# TI_POW.net
KiCad netlist of a schematic drawn in Altium Designer
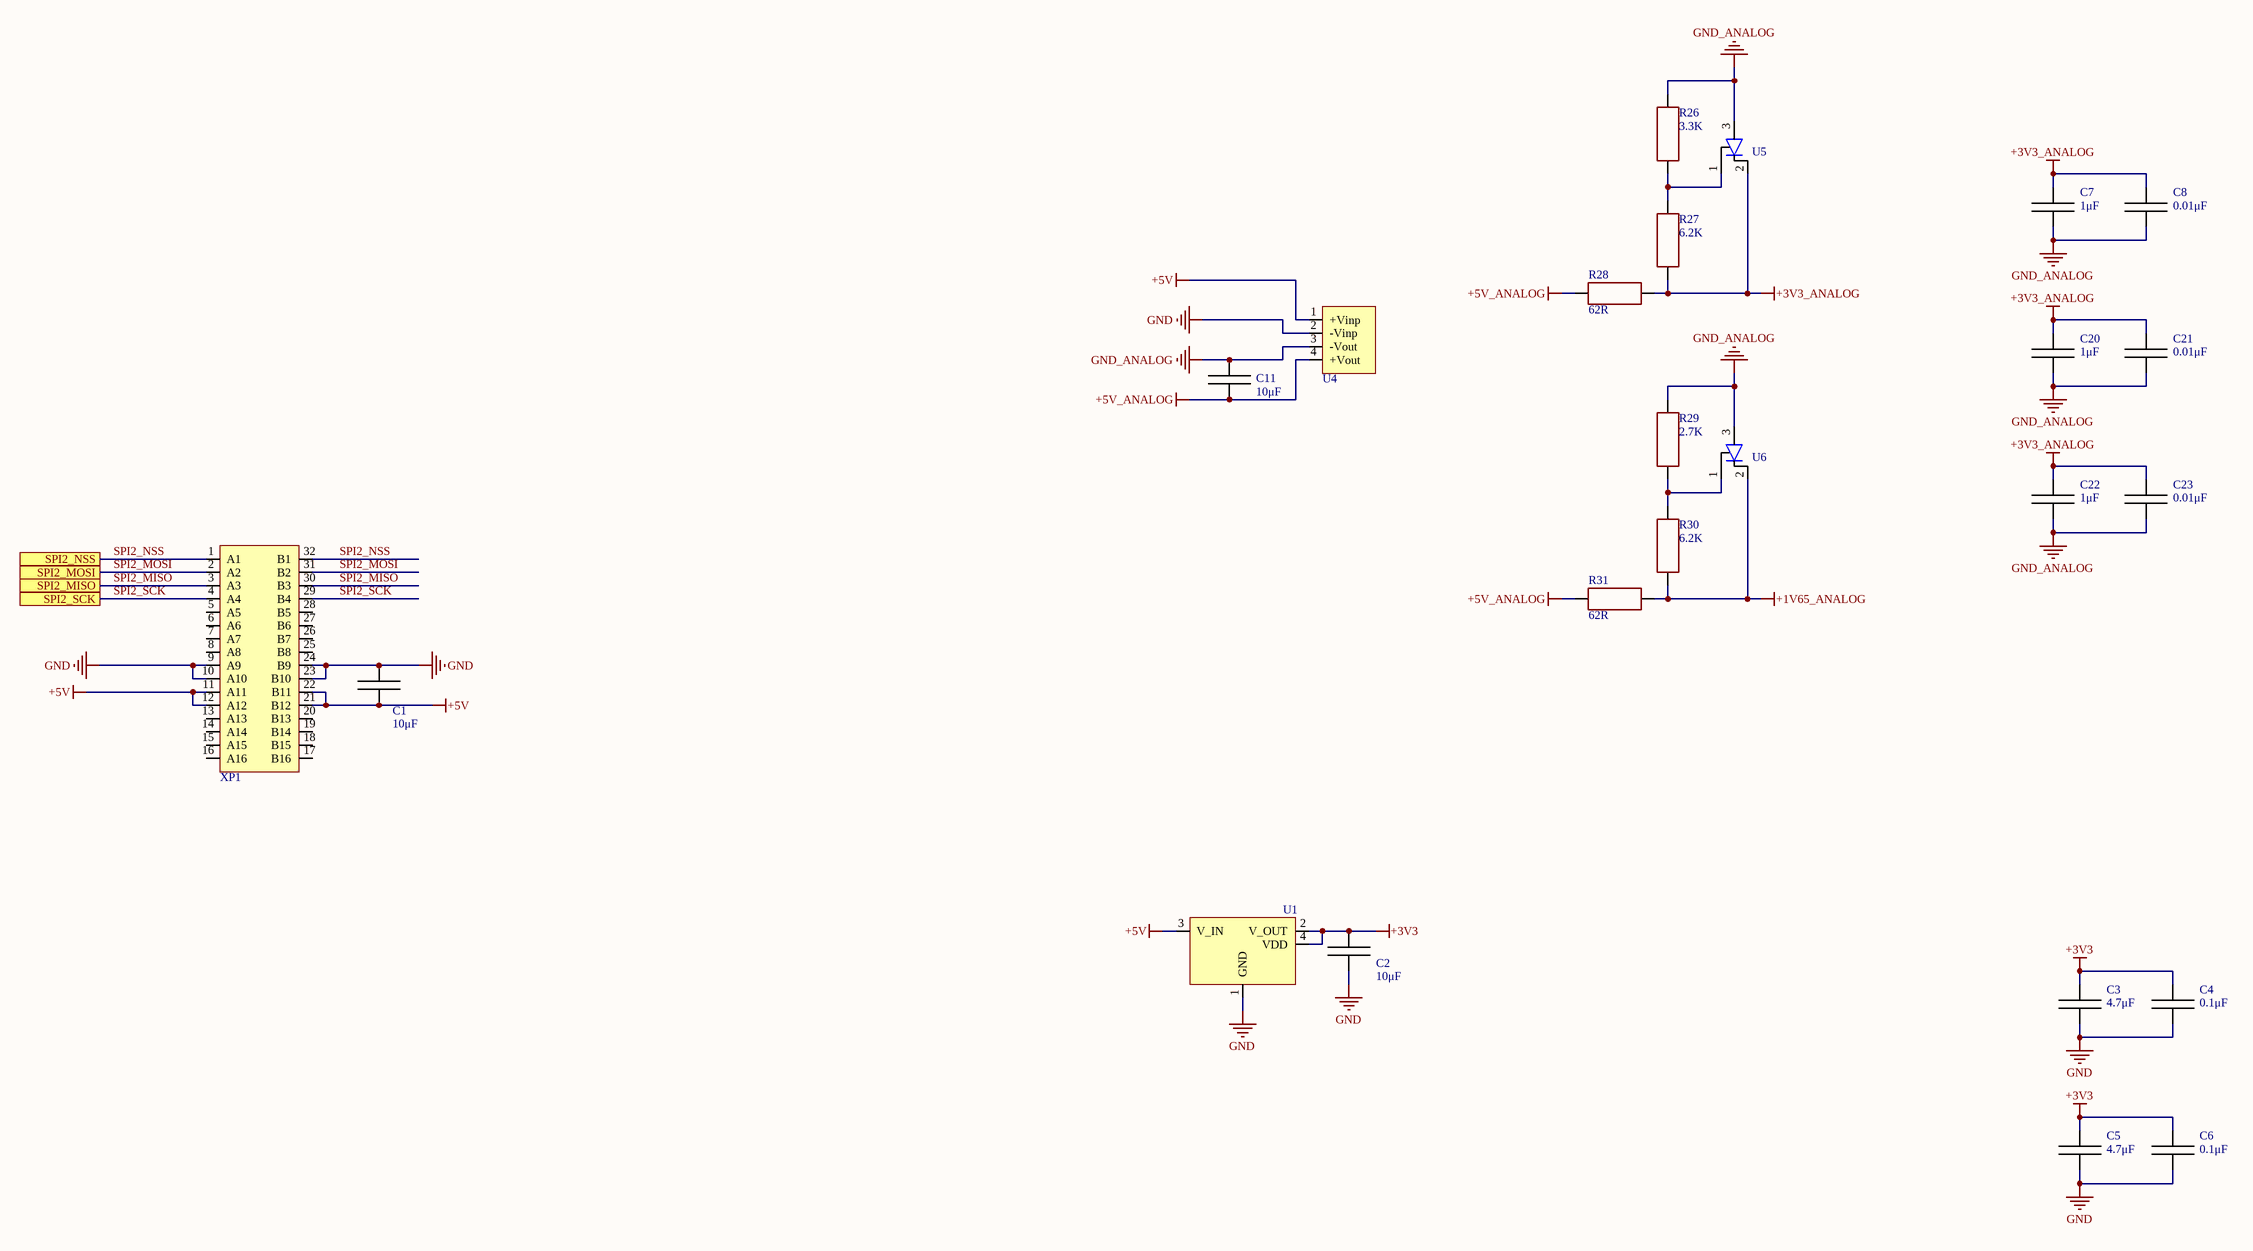
[diagram p0: TI_POW.SchDoc]

(export (version "E")
  (design (tool "Eeschema 10.0.6"))
  (components
    (comp (ref "C1")
      (value "10μF")
      (footprint "CAP: 2220")
      (fields (field (name "VOLTAGE") "16V") (field (name "Comment") "Cap_2220"))
      (libsource (lib "capacitor") (part "Cap_2220"))
    )
    (comp (ref "C2")
      (value "10μF")
      (footprint "CAP: 2220")
      (fields (field (name "VOLTAGE") "16V") (field (name "Comment") "Cap_2220"))
      (libsource (lib "capacitor") (part "Cap_2220"))
    )
    (comp (ref "C3")
      (value "4.7μF")
      (footprint "CAP: 0603")
      (fields (field (name "VOLTAGE") "25V") (field (name "Comment") "Cap_0603"))
      (libsource (lib "capacitor") (part "Cap_0603"))
    )
    (comp (ref "C4")
      (value "0.1μF")
      (footprint "CAP: 0603")
      (fields (field (name "VOLTAGE") "16V") (field (name "Comment") "Cap_0603"))
      (libsource (lib "capacitor") (part "Cap_0603"))
    )
    (comp (ref "C5")
      (value "4.7μF")
      (footprint "CAP: 0603")
      (fields (field (name "VOLTAGE") "25V") (field (name "Comment") "Cap_0603"))
      (libsource (lib "capacitor") (part "Cap_0603"))
    )
    (comp (ref "C6")
      (value "0.1μF")
      (footprint "CAP: 0603")
      (fields (field (name "VOLTAGE") "16V") (field (name "Comment") "Cap_0603"))
      (libsource (lib "capacitor") (part "Cap_0603"))
    )
    (comp (ref "C7")
      (value "1μF")
      (footprint "CAP: 0603")
      (fields (field (name "VOLTAGE") "16V") (field (name "Comment") "Cap_0603"))
      (libsource (lib "capacitor") (part "Cap_0603"))
    )
    (comp (ref "C8")
      (value "0.01μF")
      (footprint "CAP: 0603")
      (fields (field (name "VOLTAGE") "50V") (field (name "Comment") "Cap_0603"))
      (libsource (lib "capacitor") (part "Cap_0603"))
    )
    (comp (ref "C11")
      (value "10μF")
      (footprint "CAP: 2220")
      (fields (field (name "VOLTAGE") "16V") (field (name "Comment") "Cap_2220"))
      (libsource (lib "capacitor") (part "Cap_2220"))
    )
    (comp (ref "C20")
      (value "1μF")
      (footprint "CAP: 0603")
      (fields (field (name "VOLTAGE") "16V") (field (name "Comment") "Cap_0603"))
      (libsource (lib "capacitor") (part "Cap_0603"))
    )
    (comp (ref "C21")
      (value "0.01μF")
      (footprint "CAP: 0603")
      (fields (field (name "VOLTAGE") "50V") (field (name "Comment") "Cap_0603"))
      (libsource (lib "capacitor") (part "Cap_0603"))
    )
    (comp (ref "C22")
      (value "1μF")
      (footprint "CAP: 0603")
      (fields (field (name "VOLTAGE") "16V") (field (name "Comment") "Cap_0603"))
      (libsource (lib "capacitor") (part "Cap_0603"))
    )
    (comp (ref "C23")
      (value "0.01μF")
      (footprint "CAP: 0603")
      (fields (field (name "VOLTAGE") "50V") (field (name "Comment") "Cap_0603"))
      (libsource (lib "capacitor") (part "Cap_0603"))
    )
    (comp (ref "R26")
      (value "3.3K")
      (footprint "RES: 0603")
      (fields
        (field (name "POWER") "0.1W")
        (field (name "TOLERANCE") "±5%")
        (field (name "Comment") "Resistor_0603")
      )
      (libsource (lib "resistor") (part "Resistor_0603"))
    )
    (comp (ref "R27")
      (value "6.2K")
      (footprint "RES: 0603")
      (fields
        (field (name "POWER") "0.1W")
        (field (name "TOLERANCE") "±5%")
        (field (name "Comment") "Resistor_0603")
      )
      (libsource (lib "resistor") (part "Resistor_0603"))
    )
    (comp (ref "R28")
      (value "62R")
      (footprint "RES: 0603")
      (fields
        (field (name "POWER") "0.1W")
        (field (name "TOLERANCE") "±5%")
        (field (name "Comment") "Resistor_0603")
      )
      (libsource (lib "") (part "Resistor_0603_1"))
    )
    (comp (ref "R29")
      (value "2.7K")
      (footprint "RES: 0603")
      (fields
        (field (name "POWER") "0.1W")
        (field (name "TOLERANCE") "±5%")
        (field (name "Comment") "Resistor_0603")
      )
      (libsource (lib "resistor") (part "Resistor_0603"))
    )
    (comp (ref "R30")
      (value "6.2K")
      (footprint "RES: 0603")
      (fields
        (field (name "POWER") "0.1W")
        (field (name "TOLERANCE") "±5%")
        (field (name "Comment") "Resistor_0603")
      )
      (libsource (lib "resistor") (part "Resistor_0603"))
    )
    (comp (ref "R31")
      (value "62R")
      (footprint "RES: 0603")
      (fields
        (field (name "POWER") "0.1W")
        (field (name "TOLERANCE") "±5%")
        (field (name "Comment") "Resistor_0603")
      )
      (libsource (lib "") (part "Resistor_0603_1"))
    )
    (comp (ref "U1")
      (value "MCP600LD1117S33CTR4")
      (footprint "SOT-223-3")
      (description "LDO Voltage Regulator 3.3V 0.8A Positive")
      (fields (field (name "MANUFACTURER") "STMicroelectronics"))
      (libsource (lib "MY_INT_LIB") (part "LD1117S33CTR"))
    )
    (comp (ref "U4")
      (value "AM1D-0505SZ")
      (footprint "AM1D-0505SZ")
      (description "DC-DC, 5V, 0.2A")
      (fields (field (name "MANUFACTURER") "Aimtec"))
      (libsource (lib "MY_INT_LIB") (part "AM1D-0505SZ"))
    )
    (comp (ref "U5")
      (value "TLVH431BIL3T")
      (footprint "SOT-23-3")
      (description "Voltage References 1.24V to 18V Prog Shunt Ref 100uA 60mA")
      (fields (field (name "MANUFACTURER") "STMicroelectronics"))
      (libsource (lib "MY_INT_LIB") (part "TLVH431BIL3T"))
    )
    (comp (ref "U6")
      (value "TLVH431BIL3T")
      (footprint "SOT-23-3")
      (description "Voltage References 1.24V to 18V Prog Shunt Ref 100uA 60mA")
      (fields (field (name "MANUFACTURER") "STMicroelectronics"))
      (libsource (lib "MY_INT_LIB") (part "TLVH431BIL3T"))
    )
    (comp (ref "XP1")
      (value "DS1118-32M-R23")
      (footprint "DS1118-32M-R23")
      (description "DIN 41612 Connector")
      (fields (field (name "MANUFACTURER") "Connfly"))
      (libsource (lib "MY_INT_LIB") (part "DS1118-32M-R23"))
    )
  )
  (nets
    (net (code "1") (name "+1V65_ANALOG") (class "Default")
      (node (ref "R30") (pin "1") (pinfunction "1_1") (pintype "passive"))
      (node (ref "R31") (pin "1") (pinfunction "1_1") (pintype "passive"))
      (node (ref "U6") (pin "2") (pintype "passive"))
    )
    (net (code "2") (name "+3V3") (class "Default")
      (node (ref "C2") (pin "2") (pinfunction "2_2") (pintype "passive"))
      (node (ref "C3") (pin "2") (pinfunction "2_2") (pintype "passive"))
      (node (ref "C4") (pin "2") (pinfunction "2_2") (pintype "passive"))
      (node (ref "C5") (pin "2") (pinfunction "2_2") (pintype "passive"))
      (node (ref "C6") (pin "2") (pinfunction "2_2") (pintype "passive"))
      (node (ref "U1") (pin "2") (pinfunction "V_OUT_2") (pintype "power_in"))
      (node (ref "U1") (pin "4") (pinfunction "VDD_4") (pintype "power_in"))
    )
    (net (code "3") (name "+3V3_ANALOG") (class "Default")
      (node (ref "C20") (pin "2") (pinfunction "2_2") (pintype "passive"))
      (node (ref "C21") (pin "2") (pinfunction "2_2") (pintype "passive"))
      (node (ref "C22") (pin "2") (pinfunction "2_2") (pintype "passive"))
      (node (ref "C23") (pin "2") (pinfunction "2_2") (pintype "passive"))
      (node (ref "C7") (pin "2") (pinfunction "2_2") (pintype "passive"))
      (node (ref "C8") (pin "2") (pinfunction "2_2") (pintype "passive"))
      (node (ref "R27") (pin "1") (pinfunction "1_1") (pintype "passive"))
      (node (ref "R28") (pin "1") (pinfunction "1_1") (pintype "passive"))
      (node (ref "U5") (pin "2") (pintype "passive"))
    )
    (net (code "4") (name "+5V") (class "Default")
      (node (ref "C1") (pin "2") (pinfunction "2_2") (pintype "passive"))
      (node (ref "U1") (pin "3") (pinfunction "V_IN_3") (pintype "power_in"))
      (node (ref "U4") (pin "1") (pinfunction "+Vinp_1") (pintype "passive"))
      (node (ref "XP1") (pin "11") (pinfunction "A11_11") (pintype "passive"))
      (node (ref "XP1") (pin "12") (pinfunction "A12_12") (pintype "passive"))
      (node (ref "XP1") (pin "21") (pinfunction "B12_21") (pintype "passive"))
      (node (ref "XP1") (pin "22") (pinfunction "B11_22") (pintype "passive"))
    )
    (net (code "5") (name "+5V_ANALOG") (class "Default")
      (node (ref "C11") (pin "1") (pinfunction "1_1") (pintype "passive"))
      (node (ref "R28") (pin "2") (pinfunction "2_2") (pintype "passive"))
      (node (ref "R31") (pin "2") (pinfunction "2_2") (pintype "passive"))
      (node (ref "U4") (pin "4") (pinfunction "+Vout_4") (pintype "passive"))
    )
    (net (code "6") (name "/SPI2_MISO") (class "Default")
      (node (ref "XP1") (pin "3") (pinfunction "A3_3") (pintype "passive"))
      (node (ref "XP1") (pin "30") (pinfunction "B3_30") (pintype "passive"))
    )
    (net (code "7") (name "/SPI2_MOSI") (class "Default")
      (node (ref "XP1") (pin "2") (pinfunction "A2_2") (pintype "passive"))
      (node (ref "XP1") (pin "31") (pinfunction "B2_31") (pintype "passive"))
    )
    (net (code "8") (name "/SPI2_NSS") (class "Default")
      (node (ref "XP1") (pin "1") (pinfunction "A1_1") (pintype "passive"))
      (node (ref "XP1") (pin "32") (pinfunction "B1_32") (pintype "passive"))
    )
    (net (code "9") (name "/SPI2_SCK") (class "Default")
      (node (ref "XP1") (pin "29") (pinfunction "B4_29") (pintype "passive"))
      (node (ref "XP1") (pin "4") (pinfunction "A4_4") (pintype "passive"))
    )
    (net (code "10") (name "GND") (class "Default")
      (node (ref "C1") (pin "1") (pinfunction "1_1") (pintype "passive"))
      (node (ref "C2") (pin "1") (pinfunction "1_1") (pintype "passive"))
      (node (ref "C3") (pin "1") (pinfunction "1_1") (pintype "passive"))
      (node (ref "C4") (pin "1") (pinfunction "1_1") (pintype "passive"))
      (node (ref "C5") (pin "1") (pinfunction "1_1") (pintype "passive"))
      (node (ref "C6") (pin "1") (pinfunction "1_1") (pintype "passive"))
      (node (ref "U1") (pin "1") (pinfunction "GND_1") (pintype "power_in"))
      (node (ref "U4") (pin "2") (pinfunction "-Vinp_2") (pintype "passive"))
      (node (ref "XP1") (pin "10") (pinfunction "A10_10") (pintype "passive"))
      (node (ref "XP1") (pin "23") (pinfunction "B10_23") (pintype "passive"))
      (node (ref "XP1") (pin "24") (pinfunction "B9_24") (pintype "passive"))
      (node (ref "XP1") (pin "9") (pinfunction "A9_9") (pintype "passive"))
    )
    (net (code "11") (name "GND_ANALOG") (class "Default")
      (node (ref "C11") (pin "2") (pinfunction "2_2") (pintype "passive"))
      (node (ref "C20") (pin "1") (pinfunction "1_1") (pintype "passive"))
      (node (ref "C21") (pin "1") (pinfunction "1_1") (pintype "passive"))
      (node (ref "C22") (pin "1") (pinfunction "1_1") (pintype "passive"))
      (node (ref "C23") (pin "1") (pinfunction "1_1") (pintype "passive"))
      (node (ref "C7") (pin "1") (pinfunction "1_1") (pintype "passive"))
      (node (ref "C8") (pin "1") (pinfunction "1_1") (pintype "passive"))
      (node (ref "R26") (pin "2") (pinfunction "2_2") (pintype "passive"))
      (node (ref "R29") (pin "2") (pinfunction "2_2") (pintype "passive"))
      (node (ref "U4") (pin "3") (pinfunction "-Vout_3") (pintype "passive"))
      (node (ref "U5") (pin "3") (pintype "passive"))
      (node (ref "U6") (pin "3") (pintype "passive"))
    )
    (net (code "12") (name "Net-(R26-Pad1)") (class "Default")
      (node (ref "R26") (pin "1") (pinfunction "1_1") (pintype "passive"))
      (node (ref "R27") (pin "2") (pinfunction "2_2") (pintype "passive"))
      (node (ref "U5") (pin "1") (pintype "passive"))
    )
    (net (code "13") (name "Net-(R29-Pad1)") (class "Default")
      (node (ref "R29") (pin "1") (pinfunction "1_1") (pintype "passive"))
      (node (ref "R30") (pin "2") (pinfunction "2_2") (pintype "passive"))
      (node (ref "U6") (pin "1") (pintype "passive"))
    )
    (net (code "14") (name "unconnected-(XP1-A5-Pad5)") (class "Default")
      (node (ref "XP1") (pin "5") (pinfunction "A5_5") (pintype "passive"))
    )
    (net (code "15") (name "unconnected-(XP1-A6-Pad6)") (class "Default")
      (node (ref "XP1") (pin "6") (pinfunction "A6_6") (pintype "passive"))
    )
    (net (code "16") (name "unconnected-(XP1-A7-Pad7)") (class "Default")
      (node (ref "XP1") (pin "7") (pinfunction "A7_7") (pintype "passive"))
    )
    (net (code "17") (name "unconnected-(XP1-A8-Pad8)") (class "Default")
      (node (ref "XP1") (pin "8") (pinfunction "A8_8") (pintype "passive"))
    )
    (net (code "18") (name "unconnected-(XP1-A13-Pad13)") (class "Default")
      (node (ref "XP1") (pin "13") (pinfunction "A13_13") (pintype "passive"))
    )
    (net (code "19") (name "unconnected-(XP1-A14-Pad14)") (class "Default")
      (node (ref "XP1") (pin "14") (pinfunction "A14_14") (pintype "passive"))
    )
    (net (code "20") (name "unconnected-(XP1-A15-Pad15)") (class "Default")
      (node (ref "XP1") (pin "15") (pinfunction "A15_15") (pintype "passive"))
    )
    (net (code "21") (name "unconnected-(XP1-A16-Pad16)") (class "Default")
      (node (ref "XP1") (pin "16") (pinfunction "A16_16") (pintype "passive"))
    )
    (net (code "22") (name "unconnected-(XP1-B5-Pad28)") (class "Default")
      (node (ref "XP1") (pin "28") (pinfunction "B5_28") (pintype "passive"))
    )
    (net (code "23") (name "unconnected-(XP1-B6-Pad27)") (class "Default")
      (node (ref "XP1") (pin "27") (pinfunction "B6_27") (pintype "passive"))
    )
    (net (code "24") (name "unconnected-(XP1-B7-Pad26)") (class "Default")
      (node (ref "XP1") (pin "26") (pinfunction "B7_26") (pintype "passive"))
    )
    (net (code "25") (name "unconnected-(XP1-B8-Pad25)") (class "Default")
      (node (ref "XP1") (pin "25") (pinfunction "B8_25") (pintype "passive"))
    )
    (net (code "26") (name "unconnected-(XP1-B13-Pad20)") (class "Default")
      (node (ref "XP1") (pin "20") (pinfunction "B13_20") (pintype "passive"))
    )
    (net (code "27") (name "unconnected-(XP1-B14-Pad19)") (class "Default")
      (node (ref "XP1") (pin "19") (pinfunction "B14_19") (pintype "passive"))
    )
    (net (code "28") (name "unconnected-(XP1-B15-Pad18)") (class "Default")
      (node (ref "XP1") (pin "18") (pinfunction "B15_18") (pintype "passive"))
    )
    (net (code "29") (name "unconnected-(XP1-B16-Pad17)") (class "Default")
      (node (ref "XP1") (pin "17") (pinfunction "B16_17") (pintype "passive"))
    )
  )
)
